# Humus_ethernet_dip_v3.net
KiCad netlist of a schematic drawn in EAGLE
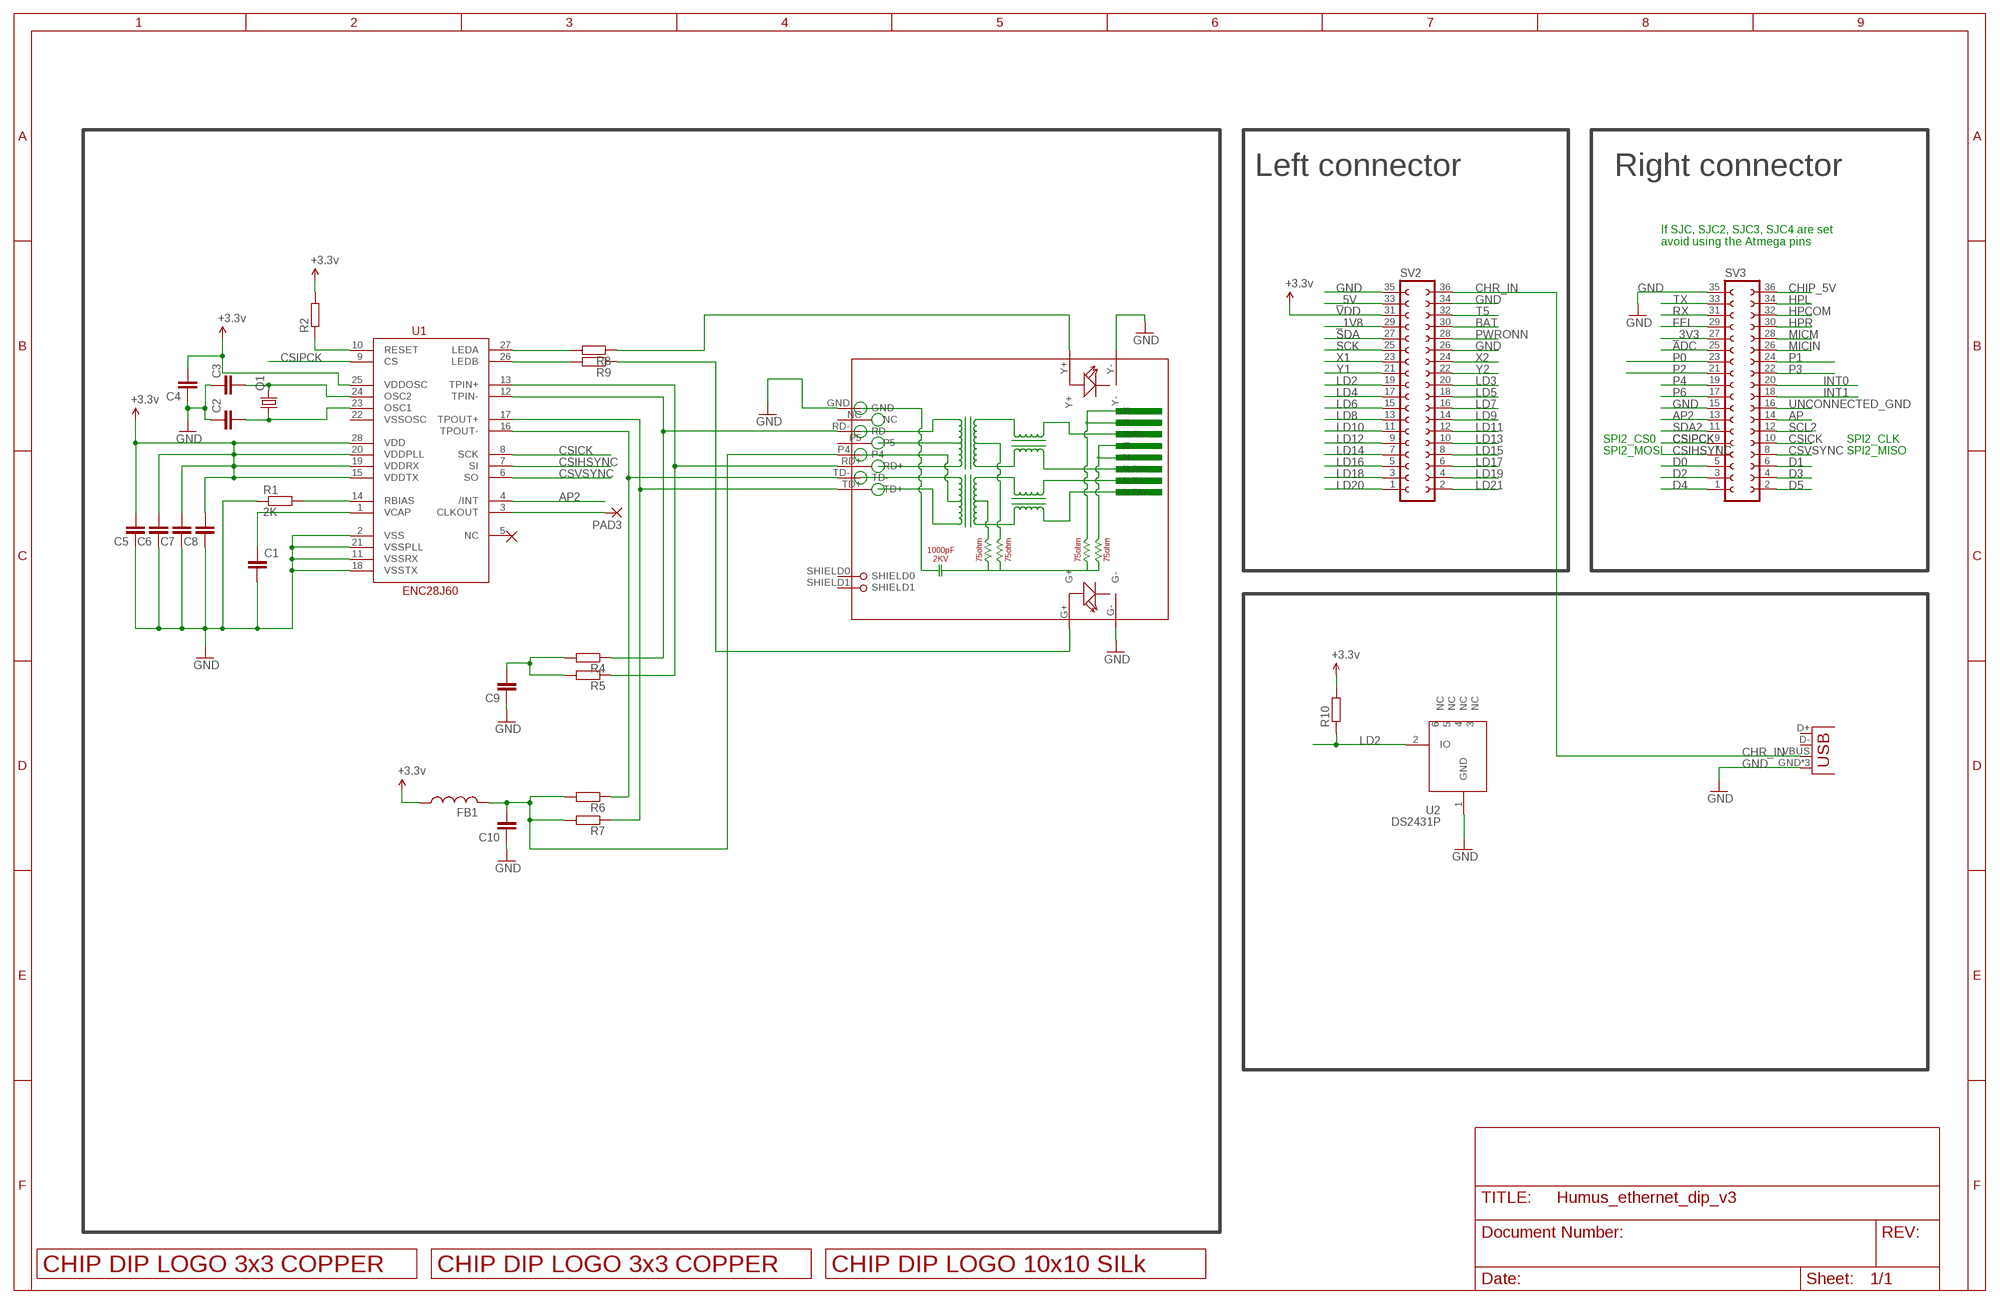
[diagram p0: schematic, sheet 1]

(export (version "E")
  (design (tool "Eeschema 10.0.6"))
  (components
    (comp (ref "C1")
      (value "C-EUC0805")
      (footprint "eagle-import:C0805")
      (libsource (lib "eagle-import") (part "C-EUC0805"))
    )
    (comp (ref "C2")
      (value "C-EUC0805")
      (footprint "eagle-import:C0805")
      (libsource (lib "eagle-import") (part "C-EUC0805"))
    )
    (comp (ref "C3")
      (value "C-EUC0805")
      (footprint "eagle-import:C0805")
      (libsource (lib "eagle-import") (part "C-EUC0805"))
    )
    (comp (ref "C4")
      (value "C-EUC0805")
      (footprint "eagle-import:C0805")
      (libsource (lib "eagle-import") (part "C-EUC0805"))
    )
    (comp (ref "C5")
      (value "C-EUC0805")
      (footprint "eagle-import:C0805")
      (libsource (lib "eagle-import") (part "C-EUC0805"))
    )
    (comp (ref "C6")
      (value "C-EUC0805")
      (footprint "eagle-import:C0805")
      (libsource (lib "eagle-import") (part "C-EUC0805"))
    )
    (comp (ref "C7")
      (value "C-EUC0805")
      (footprint "eagle-import:C0805")
      (libsource (lib "eagle-import") (part "C-EUC0805"))
    )
    (comp (ref "C8")
      (value "C-EUC0805")
      (footprint "eagle-import:C0805")
      (libsource (lib "eagle-import") (part "C-EUC0805"))
    )
    (comp (ref "C9")
      (value "C-EUC0805")
      (footprint "eagle-import:C0805")
      (libsource (lib "eagle-import") (part "C-EUC0805"))
    )
    (comp (ref "C10")
      (value "C-EUC0805")
      (footprint "eagle-import:C0805")
      (libsource (lib "eagle-import") (part "C-EUC0805"))
    )
    (comp (ref "FB1")
      (value "FERRITE-BEADB")
      (footprint "eagle-import:0805")
      (libsource (lib "eagle-import") (part "FERRITE-BEADB"))
    )
    (comp (ref "PAD3")
      (value "WIREPADSMD1,27-254")
      (footprint "eagle-import:SMD1,27-2,54")
      (libsource (lib "eagle-import") (part "WIREPADSMD1,27-254"))
    )
    (comp (ref "Q1")
      (value "CRYSTALSM49")
      (footprint "eagle-import:SM49")
      (libsource (lib "eagle-import") (part "CRYSTALSM49"))
    )
    (comp (ref "R1")
      (value "2K")
      (footprint "eagle-import:R0805")
      (libsource (lib "eagle-import") (part "R-EU_R0805"))
    )
    (comp (ref "R2")
      (value "R-EU_R0805")
      (footprint "eagle-import:R0805")
      (libsource (lib "eagle-import") (part "R-EU_R0805"))
    )
    (comp (ref "R4")
      (value "R-EU_R0805")
      (footprint "eagle-import:R0805")
      (libsource (lib "eagle-import") (part "R-EU_R0805"))
    )
    (comp (ref "R5")
      (value "R-EU_R0805")
      (footprint "eagle-import:R0805")
      (libsource (lib "eagle-import") (part "R-EU_R0805"))
    )
    (comp (ref "R6")
      (value "R-EU_R0805")
      (footprint "eagle-import:R0805")
      (libsource (lib "eagle-import") (part "R-EU_R0805"))
    )
    (comp (ref "R7")
      (value "R-EU_R0805")
      (footprint "eagle-import:R0805")
      (libsource (lib "eagle-import") (part "R-EU_R0805"))
    )
    (comp (ref "R8")
      (value "R-EU_R0805")
      (footprint "eagle-import:R0805")
      (libsource (lib "eagle-import") (part "R-EU_R0805"))
    )
    (comp (ref "R9")
      (value "R-EU_R0805")
      (footprint "eagle-import:R0805")
      (libsource (lib "eagle-import") (part "R-EU_R0805"))
    )
    (comp (ref "R10")
      (value "R-EU_R0805")
      (footprint "eagle-import:R0805")
      (libsource (lib "eagle-import") (part "R-EU_R0805"))
    )
    (comp (ref "RJ1")
      (value "HR911105A")
      (footprint "eagle-import:HR911105A")
      (libsource (lib "eagle-import") (part "HR911105A"))
    )
    (comp (ref "SV2")
      (value "FE18-2")
      (footprint "eagle-import:FE18-2")
      (libsource (lib "eagle-import") (part "FE18-2"))
    )
    (comp (ref "SV3")
      (value "FE18-2")
      (footprint "eagle-import:FE18-2")
      (libsource (lib "eagle-import") (part "FE18-2"))
    )
    (comp (ref "U$2")
      (value "LOGO_3X3_COPPER")
      (footprint "eagle-import:LOGO_3X3_COPPER")
      (libsource (lib "eagle-import") (part "LOGO_3X3_COPPER"))
    )
    (comp (ref "U$4")
      (value "LOGO_3X3_COPPER")
      (footprint "eagle-import:LOGO_3X3_COPPER")
      (libsource (lib "eagle-import") (part "LOGO_3X3_COPPER"))
    )
    (comp (ref "U$5")
      (value "LOGO_10X10_SILK")
      (footprint "eagle-import:LOGO_10X10_SILK")
      (libsource (lib "eagle-import") (part "LOGO_10X10_SILK"))
    )
    (comp (ref "U1")
      (value "ENC28J60")
      (footprint "eagle-import:SSOP28DB")
      (libsource (lib "eagle-import") (part "ENC28J60"))
    )
    (comp (ref "U2")
      (value "DS2431P")
      (footprint "eagle-import:TSOC6")
      (fields (field (name "MFG") "DIGIKEY") (field (name "VENDOR_PART_NUMBER") "DS2431P+T&R"))
      (libsource (lib "eagle-import") (part "DS2431P"))
    )
    (comp (ref "USB")
      (value "USBUSB-MICROB-SMT-DIP")
      (footprint "eagle-import:USB-MICROB-SMT-DIP")
      (libsource (lib "eagle-import") (part "USBUSB-MICROB-SMT-DIP"))
    )
  )
  (nets
    (net (code "1") (name "+3.3v") (class "Default")
      (node (ref "C4") (pin "2") (pinfunction "2_2") (pintype "passive"))
      (node (ref "C5") (pin "2") (pinfunction "2_2") (pintype "passive"))
      (node (ref "C6") (pin "2") (pinfunction "2_2") (pintype "passive"))
      (node (ref "C7") (pin "2") (pinfunction "2_2") (pintype "passive"))
      (node (ref "C8") (pin "2") (pinfunction "2_2") (pintype "passive"))
      (node (ref "FB1") (pin "1") (pinfunction "1_1") (pintype "passive"))
      (node (ref "R10") (pin "2") (pinfunction "2_2") (pintype "passive"))
      (node (ref "R2") (pin "2") (pinfunction "2_2") (pintype "passive"))
      (node (ref "SV2") (pin "31") (pinfunction "31_31") (pintype "passive"))
      (node (ref "U1") (pin "15") (pinfunction "VDDTX_15") (pintype "bidirectional"))
      (node (ref "U1") (pin "19") (pinfunction "VDDRX_19") (pintype "bidirectional"))
      (node (ref "U1") (pin "20") (pinfunction "VDDPLL_20") (pintype "bidirectional"))
      (node (ref "U1") (pin "25") (pinfunction "VDDOSC_25") (pintype "bidirectional"))
      (node (ref "U1") (pin "28") (pinfunction "VDD_28") (pintype "bidirectional"))
    )
    (net (code "2") (name "/ADC") (class "Default")
      (node (ref "SV3") (pin "25") (pinfunction "25_25") (pintype "passive"))
    )
    (net (code "3") (name "/AP") (class "Default")
      (node (ref "SV3") (pin "14") (pinfunction "14_14") (pintype "passive"))
    )
    (net (code "4") (name "/AP2") (class "Default")
      (node (ref "SV3") (pin "13") (pinfunction "13_13") (pintype "passive"))
      (node (ref "U1") (pin "4") (pinfunction "/INT_4") (pintype "bidirectional"))
    )
    (net (code "5") (name "/BAT") (class "Default")
      (node (ref "SV2") (pin "30") (pinfunction "30_30") (pintype "passive"))
    )
    (net (code "6") (name "/CHIP_5V") (class "Default")
      (node (ref "SV3") (pin "36") (pinfunction "36_36") (pintype "passive"))
    )
    (net (code "7") (name "/CHR_IN") (class "Default")
      (node (ref "SV2") (pin "36") (pinfunction "36_36") (pintype "passive"))
      (node (ref "USB") (pin "VBUS") (pinfunction "VBUS_VBUS") (pintype "bidirectional"))
    )
    (net (code "8") (name "/CSICK") (class "Default")
      (node (ref "SV3") (pin "10") (pinfunction "10_10") (pintype "passive"))
      (node (ref "U1") (pin "8") (pinfunction "SCK_8") (pintype "bidirectional"))
    )
    (net (code "9") (name "/CSIHSYNC") (class "Default")
      (node (ref "SV3") (pin "7") (pinfunction "7_7") (pintype "passive"))
      (node (ref "U1") (pin "7") (pinfunction "SI_7") (pintype "bidirectional"))
    )
    (net (code "10") (name "/CSIPCK") (class "Default")
      (node (ref "SV3") (pin "9") (pinfunction "9_9") (pintype "passive"))
      (node (ref "U1") (pin "9") (pinfunction "CS_9") (pintype "bidirectional"))
    )
    (net (code "11") (name "/CSVSYNC") (class "Default")
      (node (ref "SV3") (pin "8") (pinfunction "8_8") (pintype "passive"))
      (node (ref "U1") (pin "6") (pinfunction "SO_6") (pintype "bidirectional"))
    )
    (net (code "12") (name "/D0") (class "Default")
      (node (ref "SV3") (pin "5") (pinfunction "5_5") (pintype "passive"))
    )
    (net (code "13") (name "/D1") (class "Default")
      (node (ref "SV3") (pin "6") (pinfunction "6_6") (pintype "passive"))
    )
    (net (code "14") (name "/D2") (class "Default")
      (node (ref "SV3") (pin "3") (pinfunction "3_3") (pintype "passive"))
    )
    (net (code "15") (name "/D3") (class "Default")
      (node (ref "SV3") (pin "4") (pinfunction "4_4") (pintype "passive"))
    )
    (net (code "16") (name "/D4") (class "Default")
      (node (ref "SV3") (pin "1") (pinfunction "1_1") (pintype "passive"))
    )
    (net (code "17") (name "/D5") (class "Default")
      (node (ref "SV3") (pin "2") (pinfunction "2_2") (pintype "passive"))
    )
    (net (code "18") (name "/FEL") (class "Default")
      (node (ref "SV3") (pin "29") (pinfunction "29_29") (pintype "passive"))
    )
    (net (code "19") (name "/HPCOM") (class "Default")
      (node (ref "SV3") (pin "32") (pinfunction "32_32") (pintype "passive"))
    )
    (net (code "20") (name "/HPL") (class "Default")
      (node (ref "SV3") (pin "34") (pinfunction "34_34") (pintype "passive"))
    )
    (net (code "21") (name "/HPR") (class "Default")
      (node (ref "SV3") (pin "30") (pinfunction "30_30") (pintype "passive"))
    )
    (net (code "22") (name "/INT0") (class "Default")
      (node (ref "SV3") (pin "20") (pinfunction "20_20") (pintype "passive"))
    )
    (net (code "23") (name "/INT1") (class "Default")
      (node (ref "SV3") (pin "18") (pinfunction "18_18") (pintype "passive"))
    )
    (net (code "24") (name "/LD2") (class "Default")
      (node (ref "R10") (pin "1") (pinfunction "1_1") (pintype "passive"))
      (node (ref "SV2") (pin "19") (pinfunction "19_19") (pintype "passive"))
      (node (ref "U2") (pin "2") (pinfunction "IO_2") (pintype "bidirectional"))
    )
    (net (code "25") (name "/LD3") (class "Default")
      (node (ref "SV2") (pin "20") (pinfunction "20_20") (pintype "passive"))
    )
    (net (code "26") (name "/LD4") (class "Default")
      (node (ref "SV2") (pin "17") (pinfunction "17_17") (pintype "passive"))
    )
    (net (code "27") (name "/LD5") (class "Default")
      (node (ref "SV2") (pin "18") (pinfunction "18_18") (pintype "passive"))
    )
    (net (code "28") (name "/LD6") (class "Default")
      (node (ref "SV2") (pin "15") (pinfunction "15_15") (pintype "passive"))
    )
    (net (code "29") (name "/LD7") (class "Default")
      (node (ref "SV2") (pin "16") (pinfunction "16_16") (pintype "passive"))
    )
    (net (code "30") (name "/LD8") (class "Default")
      (node (ref "SV2") (pin "13") (pinfunction "13_13") (pintype "passive"))
    )
    (net (code "31") (name "/LD9") (class "Default")
      (node (ref "SV2") (pin "14") (pinfunction "14_14") (pintype "passive"))
    )
    (net (code "32") (name "/LD10") (class "Default")
      (node (ref "SV2") (pin "11") (pinfunction "11_11") (pintype "passive"))
    )
    (net (code "33") (name "/LD11") (class "Default")
      (node (ref "SV2") (pin "12") (pinfunction "12_12") (pintype "passive"))
    )
    (net (code "34") (name "/LD12") (class "Default")
      (node (ref "SV2") (pin "9") (pinfunction "9_9") (pintype "passive"))
    )
    (net (code "35") (name "/LD13") (class "Default")
      (node (ref "SV2") (pin "10") (pinfunction "10_10") (pintype "passive"))
    )
    (net (code "36") (name "/LD14") (class "Default")
      (node (ref "SV2") (pin "7") (pinfunction "7_7") (pintype "passive"))
    )
    (net (code "37") (name "/LD15") (class "Default")
      (node (ref "SV2") (pin "8") (pinfunction "8_8") (pintype "passive"))
    )
    (net (code "38") (name "/LD16") (class "Default")
      (node (ref "SV2") (pin "5") (pinfunction "5_5") (pintype "passive"))
    )
    (net (code "39") (name "/LD17") (class "Default")
      (node (ref "SV2") (pin "6") (pinfunction "6_6") (pintype "passive"))
    )
    (net (code "40") (name "/LD18") (class "Default")
      (node (ref "SV2") (pin "3") (pinfunction "3_3") (pintype "passive"))
    )
    (net (code "41") (name "/LD19") (class "Default")
      (node (ref "SV2") (pin "4") (pinfunction "4_4") (pintype "passive"))
    )
    (net (code "42") (name "/LD20") (class "Default")
      (node (ref "SV2") (pin "1") (pinfunction "1_1") (pintype "passive"))
    )
    (net (code "43") (name "/LD21") (class "Default")
      (node (ref "SV2") (pin "2") (pinfunction "2_2") (pintype "passive"))
    )
    (net (code "44") (name "/MICIN") (class "Default")
      (node (ref "SV3") (pin "26") (pinfunction "26_26") (pintype "passive"))
    )
    (net (code "45") (name "/MICM") (class "Default")
      (node (ref "SV3") (pin "28") (pinfunction "28_28") (pintype "passive"))
    )
    (net (code "46") (name "/P0") (class "Default")
      (node (ref "SV3") (pin "23") (pinfunction "23_23") (pintype "passive"))
    )
    (net (code "47") (name "/P1") (class "Default")
      (node (ref "SV3") (pin "24") (pinfunction "24_24") (pintype "passive"))
    )
    (net (code "48") (name "/P2") (class "Default")
      (node (ref "SV3") (pin "21") (pinfunction "21_21") (pintype "passive"))
    )
    (net (code "49") (name "/P3") (class "Default")
      (node (ref "SV3") (pin "22") (pinfunction "22_22") (pintype "passive"))
    )
    (net (code "50") (name "/P4") (class "Default")
      (node (ref "SV3") (pin "19") (pinfunction "19_19") (pintype "passive"))
    )
    (net (code "51") (name "/P6") (class "Default")
      (node (ref "SV3") (pin "17") (pinfunction "17_17") (pintype "passive"))
    )
    (net (code "52") (name "/PWRONN") (class "Default")
      (node (ref "SV2") (pin "28") (pinfunction "28_28") (pintype "passive"))
    )
    (net (code "53") (name "/RX") (class "Default")
      (node (ref "SV3") (pin "31") (pinfunction "31_31") (pintype "passive"))
    )
    (net (code "54") (name "/SCK") (class "Default")
      (node (ref "SV2") (pin "25") (pinfunction "25_25") (pintype "passive"))
    )
    (net (code "55") (name "/SCL2") (class "Default")
      (node (ref "SV3") (pin "12") (pinfunction "12_12") (pintype "passive"))
    )
    (net (code "56") (name "/SDA") (class "Default")
      (node (ref "SV2") (pin "27") (pinfunction "27_27") (pintype "passive"))
    )
    (net (code "57") (name "/SDA2") (class "Default")
      (node (ref "SV3") (pin "11") (pinfunction "11_11") (pintype "passive"))
    )
    (net (code "58") (name "/T5") (class "Default")
      (node (ref "SV2") (pin "32") (pinfunction "32_32") (pintype "passive"))
    )
    (net (code "59") (name "/TX") (class "Default")
      (node (ref "SV3") (pin "33") (pinfunction "33_33") (pintype "passive"))
    )
    (net (code "60") (name "/UNCONNECTED_GND") (class "Default")
      (node (ref "SV3") (pin "16") (pinfunction "16_16") (pintype "passive"))
    )
    (net (code "61") (name "/X1") (class "Default")
      (node (ref "SV2") (pin "23") (pinfunction "23_23") (pintype "passive"))
    )
    (net (code "62") (name "/X2") (class "Default")
      (node (ref "SV2") (pin "24") (pinfunction "24_24") (pintype "passive"))
    )
    (net (code "63") (name "/Y1") (class "Default")
      (node (ref "SV2") (pin "21") (pinfunction "21_21") (pintype "passive"))
    )
    (net (code "64") (name "/Y2") (class "Default")
      (node (ref "SV2") (pin "22") (pinfunction "22_22") (pintype "passive"))
    )
    (net (code "65") (name "/_1V8") (class "Default")
      (node (ref "SV2") (pin "29") (pinfunction "29_29") (pintype "passive"))
    )
    (net (code "66") (name "/_3V3") (class "Default")
      (node (ref "SV3") (pin "27") (pinfunction "27_27") (pintype "passive"))
    )
    (net (code "67") (name "/_5V") (class "Default")
      (node (ref "SV2") (pin "33") (pinfunction "33_33") (pintype "passive"))
    )
    (net (code "68") (name "GND") (class "Default")
      (node (ref "C1") (pin "2") (pinfunction "2_2") (pintype "passive"))
      (node (ref "C10") (pin "1") (pinfunction "1_1") (pintype "passive"))
      (node (ref "C2") (pin "1") (pinfunction "1_1") (pintype "passive"))
      (node (ref "C3") (pin "1") (pinfunction "1_1") (pintype "passive"))
      (node (ref "C4") (pin "1") (pinfunction "1_1") (pintype "passive"))
      (node (ref "C5") (pin "1") (pinfunction "1_1") (pintype "passive"))
      (node (ref "C6") (pin "1") (pinfunction "1_1") (pintype "passive"))
      (node (ref "C7") (pin "1") (pinfunction "1_1") (pintype "passive"))
      (node (ref "C8") (pin "1") (pinfunction "1_1") (pintype "passive"))
      (node (ref "C9") (pin "1") (pinfunction "1_1") (pintype "passive"))
      (node (ref "R1") (pin "1") (pinfunction "1_1") (pintype "passive"))
      (node (ref "RJ1") (pin "G-") (pinfunction "G-_G-") (pintype "bidirectional"))
      (node (ref "RJ1") (pin "GND") (pinfunction "GND_GND") (pintype "bidirectional"))
      (node (ref "RJ1") (pin "Y-") (pinfunction "Y-_Y-") (pintype "bidirectional"))
      (node (ref "SV2") (pin "26") (pinfunction "26_26") (pintype "passive"))
      (node (ref "SV2") (pin "34") (pinfunction "34_34") (pintype "passive"))
      (node (ref "SV2") (pin "35") (pinfunction "35_35") (pintype "passive"))
      (node (ref "SV3") (pin "15") (pinfunction "15_15") (pintype "passive"))
      (node (ref "SV3") (pin "35") (pinfunction "35_35") (pintype "passive"))
      (node (ref "U1") (pin "11") (pinfunction "VSSRX_11") (pintype "bidirectional"))
      (node (ref "U1") (pin "18") (pinfunction "VSSTX_18") (pintype "bidirectional"))
      (node (ref "U1") (pin "2") (pinfunction "VSS_2") (pintype "bidirectional"))
      (node (ref "U1") (pin "21") (pinfunction "VSSPLL_21") (pintype "bidirectional"))
      (node (ref "U2") (pin "1") (pinfunction "GND_1") (pintype "bidirectional"))
      (node (ref "USB") (pin "GND") (pinfunction "GND_GND") (pintype "bidirectional"))
      (node (ref "USB") (pin "MT1") (pinfunction "GND_MT1") (pintype "bidirectional"))
      (node (ref "USB") (pin "MT2") (pinfunction "GND_MT2") (pintype "bidirectional"))
    )
    (net (code "69") (name "Net-(C9-Pad2)") (class "Default")
      (node (ref "C9") (pin "2") (pinfunction "2_2") (pintype "passive"))
      (node (ref "R4") (pin "2") (pinfunction "2_2") (pintype "passive"))
      (node (ref "R5") (pin "2") (pinfunction "2_2") (pintype "passive"))
    )
    (net (code "70") (name "Net-(C10-Pad2)") (class "Default")
      (node (ref "C10") (pin "2") (pinfunction "2_2") (pintype "passive"))
      (node (ref "FB1") (pin "2") (pinfunction "2_2") (pintype "passive"))
      (node (ref "R6") (pin "2") (pinfunction "2_2") (pintype "passive"))
      (node (ref "R7") (pin "2") (pinfunction "2_2") (pintype "passive"))
      (node (ref "RJ1") (pin "P4") (pinfunction "P4_P4") (pintype "bidirectional"))
    )
    (net (code "71") (name "Net-(PAD3-P)") (class "Default")
      (node (ref "PAD3") (pin "1") (pinfunction "P_1") (pintype "passive"))
      (node (ref "U1") (pin "3") (pinfunction "CLKOUT_3") (pintype "bidirectional"))
    )
    (net (code "72") (name "Net-(R8-Pad1)") (class "Default")
      (node (ref "R8") (pin "1") (pinfunction "1_1") (pintype "passive"))
      (node (ref "RJ1") (pin "Y+") (pinfunction "Y+_Y+") (pintype "bidirectional"))
    )
    (net (code "73") (name "Net-(R9-Pad1)") (class "Default")
      (node (ref "R9") (pin "1") (pinfunction "1_1") (pintype "passive"))
      (node (ref "RJ1") (pin "G+") (pinfunction "G+_G+") (pintype "bidirectional"))
    )
    (net (code "74") (name "Net-(U1-LEDA)") (class "Default")
      (node (ref "R8") (pin "2") (pinfunction "2_2") (pintype "passive"))
      (node (ref "U1") (pin "27") (pinfunction "LEDA_27") (pintype "bidirectional"))
    )
    (net (code "75") (name "Net-(U1-LEDB)") (class "Default")
      (node (ref "R9") (pin "2") (pinfunction "2_2") (pintype "passive"))
      (node (ref "U1") (pin "26") (pinfunction "LEDB_26") (pintype "bidirectional"))
    )
    (net (code "76") (name "Net-(U1-OSC1)") (class "Default")
      (node (ref "C2") (pin "2") (pinfunction "2_2") (pintype "passive"))
      (node (ref "Q1") (pin "1") (pinfunction "1_1") (pintype "passive"))
      (node (ref "U1") (pin "23") (pinfunction "OSC1_23") (pintype "bidirectional"))
    )
    (net (code "77") (name "Net-(U1-OSC2)") (class "Default")
      (node (ref "C3") (pin "2") (pinfunction "2_2") (pintype "passive"))
      (node (ref "Q1") (pin "2") (pinfunction "2_2") (pintype "passive"))
      (node (ref "U1") (pin "24") (pinfunction "OSC2_24") (pintype "bidirectional"))
    )
    (net (code "78") (name "Net-(U1-RBIAS)") (class "Default")
      (node (ref "R1") (pin "2") (pinfunction "2_2") (pintype "passive"))
      (node (ref "U1") (pin "14") (pinfunction "RBIAS_14") (pintype "bidirectional"))
    )
    (net (code "79") (name "Net-(U1-RESET)") (class "Default")
      (node (ref "R2") (pin "1") (pinfunction "1_1") (pintype "passive"))
      (node (ref "U1") (pin "10") (pinfunction "RESET_10") (pintype "bidirectional"))
    )
    (net (code "80") (name "Net-(U1-TPIN+)") (class "Default")
      (node (ref "R5") (pin "1") (pinfunction "1_1") (pintype "passive"))
      (node (ref "RJ1") (pin "RD+") (pinfunction "RD+_RD+") (pintype "bidirectional"))
      (node (ref "U1") (pin "13") (pinfunction "TPIN+_13") (pintype "bidirectional"))
    )
    (net (code "81") (name "Net-(U1-TPIN-)") (class "Default")
      (node (ref "R4") (pin "1") (pinfunction "1_1") (pintype "passive"))
      (node (ref "RJ1") (pin "RD-") (pinfunction "RD-_RD-") (pintype "bidirectional"))
      (node (ref "U1") (pin "12") (pinfunction "TPIN-_12") (pintype "bidirectional"))
    )
    (net (code "82") (name "Net-(U1-TPOUT+)") (class "Default")
      (node (ref "R7") (pin "1") (pinfunction "1_1") (pintype "passive"))
      (node (ref "RJ1") (pin "TD+") (pinfunction "TD+_TD+") (pintype "bidirectional"))
      (node (ref "U1") (pin "17") (pinfunction "TPOUT+_17") (pintype "bidirectional"))
    )
    (net (code "83") (name "Net-(U1-TPOUT-)") (class "Default")
      (node (ref "R6") (pin "1") (pinfunction "1_1") (pintype "passive"))
      (node (ref "RJ1") (pin "TD-") (pinfunction "TD-_TD-") (pintype "bidirectional"))
      (node (ref "U1") (pin "16") (pinfunction "TPOUT-_16") (pintype "bidirectional"))
    )
    (net (code "84") (name "Net-(U1-VCAP)") (class "Default")
      (node (ref "C1") (pin "1") (pinfunction "1_1") (pintype "passive"))
      (node (ref "U1") (pin "1") (pinfunction "VCAP_1") (pintype "bidirectional"))
    )
    (net (code "85") (name "unconnected-(RJ1-PadNC)") (class "Default")
      (node (ref "RJ1") (pin "NC") (pinfunction "NC_NC") (pintype "bidirectional"))
    )
    (net (code "86") (name "unconnected-(RJ1-PadP5)") (class "Default")
      (node (ref "RJ1") (pin "P5") (pinfunction "P5_P5") (pintype "bidirectional"))
    )
    (net (code "87") (name "unconnected-(RJ1-PadSHIELD0)") (class "Default")
      (node (ref "RJ1") (pin "SHIELD0") (pinfunction "SHIELD0_SHIELD0") (pintype "bidirectional"))
    )
    (net (code "88") (name "unconnected-(RJ1-PadSHIELD1)") (class "Default")
      (node (ref "RJ1") (pin "SHIELD1") (pinfunction "SHIELD1_SHIELD1") (pintype "bidirectional"))
    )
    (net (code "89") (name "unconnected-(U1-NC-Pad5)") (class "Default")
      (node (ref "U1") (pin "5") (pinfunction "NC_5") (pintype "bidirectional"))
    )
    (net (code "90") (name "unconnected-(U1-VSSOSC-Pad22)") (class "Default")
      (node (ref "U1") (pin "22") (pinfunction "VSSOSC_22") (pintype "bidirectional"))
    )
    (net (code "91") (name "unconnected-(U2-NC-Pad3)") (class "Default")
      (node (ref "U2") (pin "3") (pinfunction "NC_3") (pintype "bidirectional"))
    )
    (net (code "92") (name "unconnected-(U2-NC-Pad4)") (class "Default")
      (node (ref "U2") (pin "4") (pinfunction "NC_4") (pintype "bidirectional"))
    )
    (net (code "93") (name "unconnected-(U2-NC-Pad5)") (class "Default")
      (node (ref "U2") (pin "5") (pinfunction "NC_5") (pintype "bidirectional"))
    )
    (net (code "94") (name "unconnected-(U2-NC-Pad6)") (class "Default")
      (node (ref "U2") (pin "6") (pinfunction "NC_6") (pintype "bidirectional"))
    )
    (net (code "95") (name "unconnected-(USB-PadD+)") (class "Default")
      (node (ref "USB") (pin "D+") (pinfunction "D+_D+") (pintype "bidirectional"))
    )
    (net (code "96") (name "unconnected-(USB-PadD-)") (class "Default")
      (node (ref "USB") (pin "D-") (pinfunction "D-_D-") (pintype "bidirectional"))
    )
  )
)
